# binary_watch_shield_v1.net
KiCad netlist of a schematic drawn in EAGLE
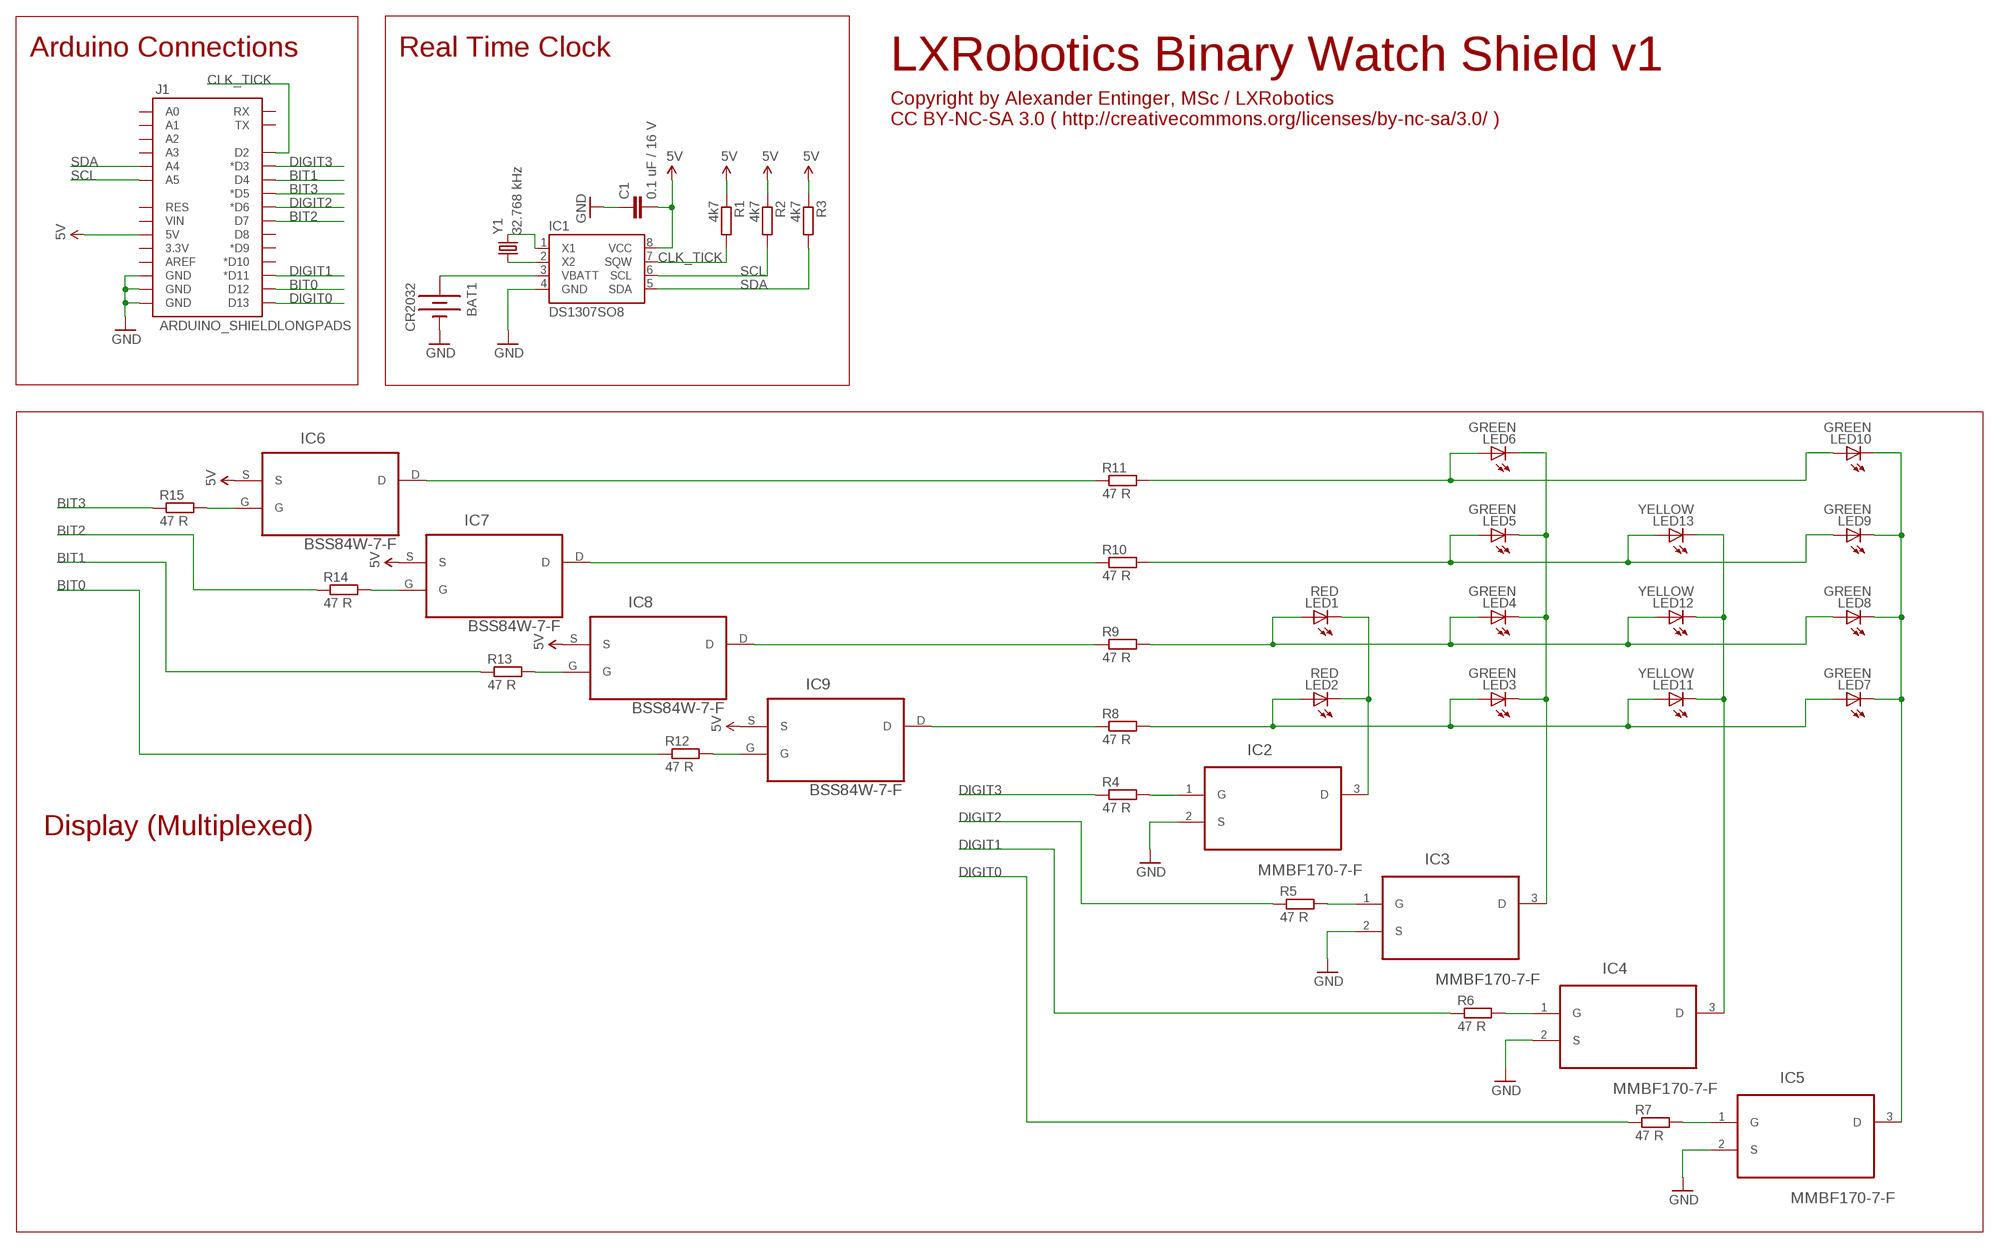
[diagram p0: schematic, sheet 1]

(export (version "E")
  (design (tool "Eeschema 10.0.6"))
  (components
    (comp (ref "BAT1")
      (value "CR2032")
      (footprint "eagle-import:BATTCON_20MM")
      (libsource (lib "eagle-import") (part "BATTERY20SMD"))
    )
    (comp (ref "C1")
      (value "0.1 uF / 16 V")
      (footprint "eagle-import:C0805")
      (libsource (lib "eagle-import") (part "C-EUC0805"))
    )
    (comp (ref "IC1")
      (value "DS1307SO8")
      (footprint "eagle-import:SO08")
      (libsource (lib "eagle-import") (part "DS1307SO8"))
    )
    (comp (ref "IC2")
      (value "MMBF170-7-F")
      (footprint "eagle-import:SOT103P240X110-3N")
      (libsource (lib "eagle-import") (part "MMBF170-7-F"))
    )
    (comp (ref "IC3")
      (value "MMBF170-7-F")
      (footprint "eagle-import:SOT103P240X110-3N")
      (libsource (lib "eagle-import") (part "MMBF170-7-F"))
    )
    (comp (ref "IC4")
      (value "MMBF170-7-F")
      (footprint "eagle-import:SOT103P240X110-3N")
      (libsource (lib "eagle-import") (part "MMBF170-7-F"))
    )
    (comp (ref "IC5")
      (value "MMBF170-7-F")
      (footprint "eagle-import:SOT103P240X110-3N")
      (libsource (lib "eagle-import") (part "MMBF170-7-F"))
    )
    (comp (ref "IC6")
      (value "BSS84W-7-F")
      (footprint "eagle-import:SOT65P210X110-3N")
      (libsource (lib "eagle-import") (part "BSS84W-7-F"))
    )
    (comp (ref "IC7")
      (value "BSS84W-7-F")
      (footprint "eagle-import:SOT65P210X110-3N")
      (libsource (lib "eagle-import") (part "BSS84W-7-F"))
    )
    (comp (ref "IC8")
      (value "BSS84W-7-F")
      (footprint "eagle-import:SOT65P210X110-3N")
      (libsource (lib "eagle-import") (part "BSS84W-7-F"))
    )
    (comp (ref "IC9")
      (value "BSS84W-7-F")
      (footprint "eagle-import:SOT65P210X110-3N")
      (libsource (lib "eagle-import") (part "BSS84W-7-F"))
    )
    (comp (ref "J1")
      (value "ARDUINO_SHIELDLONGPADS")
      (footprint "eagle-import:DUEMILANOVE_SHIELD_LONGPADS")
      (libsource (lib "eagle-import") (part "ARDUINO_SHIELDLONGPADS"))
    )
    (comp (ref "LED1")
      (value "RED")
      (footprint "eagle-import:LED5MM")
      (libsource (lib "eagle-import") (part "LED5MM"))
    )
    (comp (ref "LED2")
      (value "RED")
      (footprint "eagle-import:LED5MM")
      (libsource (lib "eagle-import") (part "LED5MM"))
    )
    (comp (ref "LED3")
      (value "GREEN")
      (footprint "eagle-import:LED5MM")
      (libsource (lib "eagle-import") (part "LED5MM"))
    )
    (comp (ref "LED4")
      (value "GREEN")
      (footprint "eagle-import:LED5MM")
      (libsource (lib "eagle-import") (part "LED5MM"))
    )
    (comp (ref "LED5")
      (value "GREEN")
      (footprint "eagle-import:LED5MM")
      (libsource (lib "eagle-import") (part "LED5MM"))
    )
    (comp (ref "LED6")
      (value "GREEN")
      (footprint "eagle-import:LED5MM")
      (libsource (lib "eagle-import") (part "LED5MM"))
    )
    (comp (ref "LED7")
      (value "GREEN")
      (footprint "eagle-import:LED5MM")
      (libsource (lib "eagle-import") (part "LED5MM"))
    )
    (comp (ref "LED8")
      (value "GREEN")
      (footprint "eagle-import:LED5MM")
      (libsource (lib "eagle-import") (part "LED5MM"))
    )
    (comp (ref "LED9")
      (value "GREEN")
      (footprint "eagle-import:LED5MM")
      (libsource (lib "eagle-import") (part "LED5MM"))
    )
    (comp (ref "LED10")
      (value "GREEN")
      (footprint "eagle-import:LED5MM")
      (libsource (lib "eagle-import") (part "LED5MM"))
    )
    (comp (ref "LED11")
      (value "YELLOW")
      (footprint "eagle-import:LED5MM")
      (libsource (lib "eagle-import") (part "LED5MM"))
    )
    (comp (ref "LED12")
      (value "YELLOW")
      (footprint "eagle-import:LED5MM")
      (libsource (lib "eagle-import") (part "LED5MM"))
    )
    (comp (ref "LED13")
      (value "YELLOW")
      (footprint "eagle-import:LED5MM")
      (libsource (lib "eagle-import") (part "LED5MM"))
    )
    (comp (ref "R1")
      (value "4k7")
      (footprint "eagle-import:R0805")
      (libsource (lib "eagle-import") (part "R-EU_R0805"))
    )
    (comp (ref "R2")
      (value "4k7")
      (footprint "eagle-import:R0805")
      (libsource (lib "eagle-import") (part "R-EU_R0805"))
    )
    (comp (ref "R3")
      (value "4k7")
      (footprint "eagle-import:R0805")
      (libsource (lib "eagle-import") (part "R-EU_R0805"))
    )
    (comp (ref "R4")
      (value "47 R")
      (footprint "eagle-import:R0805")
      (libsource (lib "eagle-import") (part "R-EU_R0805"))
    )
    (comp (ref "R5")
      (value "47 R")
      (footprint "eagle-import:R0805")
      (libsource (lib "eagle-import") (part "R-EU_R0805"))
    )
    (comp (ref "R6")
      (value "47 R")
      (footprint "eagle-import:R0805")
      (libsource (lib "eagle-import") (part "R-EU_R0805"))
    )
    (comp (ref "R7")
      (value "47 R")
      (footprint "eagle-import:R0805")
      (libsource (lib "eagle-import") (part "R-EU_R0805"))
    )
    (comp (ref "R8")
      (value "47 R")
      (footprint "eagle-import:R0805")
      (libsource (lib "eagle-import") (part "R-EU_R0805"))
    )
    (comp (ref "R9")
      (value "47 R")
      (footprint "eagle-import:R0805")
      (libsource (lib "eagle-import") (part "R-EU_R0805"))
    )
    (comp (ref "R10")
      (value "47 R")
      (footprint "eagle-import:R0805")
      (libsource (lib "eagle-import") (part "R-EU_R0805"))
    )
    (comp (ref "R11")
      (value "47 R")
      (footprint "eagle-import:R0805")
      (libsource (lib "eagle-import") (part "R-EU_R0805"))
    )
    (comp (ref "R12")
      (value "47 R")
      (footprint "eagle-import:R0805")
      (libsource (lib "eagle-import") (part "R-EU_R0805"))
    )
    (comp (ref "R13")
      (value "47 R")
      (footprint "eagle-import:R0805")
      (libsource (lib "eagle-import") (part "R-EU_R0805"))
    )
    (comp (ref "R14")
      (value "47 R")
      (footprint "eagle-import:R0805")
      (libsource (lib "eagle-import") (part "R-EU_R0805"))
    )
    (comp (ref "R15")
      (value "47 R")
      (footprint "eagle-import:R0805")
      (libsource (lib "eagle-import") (part "R-EU_R0805"))
    )
    (comp (ref "Y1")
      (value "32.768 kHz")
      (footprint "eagle-import:TC26HEZ")
      (libsource (lib "eagle-import") (part "CRYSTALTC26H_EZ"))
    )
  )
  (nets
    (net (code "1") (name "/BIT0") (class "Default")
      (node (ref "J1") (pin "D12") (pinfunction "D12_D12") (pintype "bidirectional"))
      (node (ref "R12") (pin "1") (pinfunction "1_1") (pintype "passive"))
    )
    (net (code "2") (name "/BIT1") (class "Default")
      (node (ref "J1") (pin "D4") (pinfunction "D4_D4") (pintype "bidirectional"))
      (node (ref "R13") (pin "1") (pinfunction "1_1") (pintype "passive"))
    )
    (net (code "3") (name "/BIT2") (class "Default")
      (node (ref "J1") (pin "D7") (pinfunction "D7_D7") (pintype "bidirectional"))
      (node (ref "R14") (pin "1") (pinfunction "1_1") (pintype "passive"))
    )
    (net (code "4") (name "/BIT3") (class "Default")
      (node (ref "J1") (pin "D5") (pinfunction "*D5_D5") (pintype "bidirectional"))
      (node (ref "R15") (pin "1") (pinfunction "1_1") (pintype "passive"))
    )
    (net (code "5") (name "/CLK_TICK") (class "Default")
      (node (ref "IC1") (pin "7") (pinfunction "SQW_7") (pintype "bidirectional"))
      (node (ref "J1") (pin "D2") (pinfunction "D2_D2") (pintype "bidirectional"))
      (node (ref "R1") (pin "2") (pinfunction "2_2") (pintype "passive"))
    )
    (net (code "6") (name "/DIGIT0") (class "Default")
      (node (ref "J1") (pin "D13") (pinfunction "D13_D13") (pintype "bidirectional"))
      (node (ref "R7") (pin "1") (pinfunction "1_1") (pintype "passive"))
    )
    (net (code "7") (name "/DIGIT1") (class "Default")
      (node (ref "J1") (pin "D11") (pinfunction "*D11_D11") (pintype "bidirectional"))
      (node (ref "R6") (pin "1") (pinfunction "1_1") (pintype "passive"))
    )
    (net (code "8") (name "/DIGIT2") (class "Default")
      (node (ref "J1") (pin "D6") (pinfunction "*D6_D6") (pintype "bidirectional"))
      (node (ref "R5") (pin "1") (pinfunction "1_1") (pintype "passive"))
    )
    (net (code "9") (name "/DIGIT3") (class "Default")
      (node (ref "J1") (pin "D3") (pinfunction "*D3_D3") (pintype "bidirectional"))
      (node (ref "R4") (pin "1") (pinfunction "1_1") (pintype "passive"))
    )
    (net (code "10") (name "/SCL") (class "Default")
      (node (ref "IC1") (pin "6") (pinfunction "SCL_6") (pintype "bidirectional"))
      (node (ref "J1") (pin "A5") (pinfunction "A5_A5") (pintype "bidirectional"))
      (node (ref "R2") (pin "2") (pinfunction "2_2") (pintype "passive"))
    )
    (net (code "11") (name "/SDA") (class "Default")
      (node (ref "IC1") (pin "5") (pinfunction "SDA_5") (pintype "bidirectional"))
      (node (ref "J1") (pin "A4") (pinfunction "A4_A4") (pintype "bidirectional"))
      (node (ref "R3") (pin "2") (pinfunction "2_2") (pintype "passive"))
    )
    (net (code "12") (name "5V") (class "Default")
      (node (ref "C1") (pin "2") (pinfunction "2_2") (pintype "passive"))
      (node (ref "IC1") (pin "8") (pinfunction "VCC_8") (pintype "bidirectional"))
      (node (ref "IC6") (pin "S") (pinfunction "S_S") (pintype "input"))
      (node (ref "IC7") (pin "S") (pinfunction "S_S") (pintype "input"))
      (node (ref "IC8") (pin "S") (pinfunction "S_S") (pintype "input"))
      (node (ref "IC9") (pin "S") (pinfunction "S_S") (pintype "input"))
      (node (ref "J1") (pin "5V") (pinfunction "5V_5V") (pintype "bidirectional"))
      (node (ref "R1") (pin "1") (pinfunction "1_1") (pintype "passive"))
      (node (ref "R2") (pin "1") (pinfunction "1_1") (pintype "passive"))
      (node (ref "R3") (pin "1") (pinfunction "1_1") (pintype "passive"))
    )
    (net (code "13") (name "GND") (class "Default")
      (node (ref "BAT1") (pin "2") (pinfunction "-_2") (pintype "power_in"))
      (node (ref "C1") (pin "1") (pinfunction "1_1") (pintype "passive"))
      (node (ref "IC1") (pin "4") (pinfunction "GND_4") (pintype "bidirectional"))
      (node (ref "IC2") (pin "2") (pinfunction "S_2") (pintype "passive"))
      (node (ref "IC3") (pin "2") (pinfunction "S_2") (pintype "passive"))
      (node (ref "IC4") (pin "2") (pinfunction "S_2") (pintype "passive"))
      (node (ref "IC5") (pin "2") (pinfunction "S_2") (pintype "passive"))
      (node (ref "J1") (pin "GND@0") (pinfunction "GND_GND@0") (pintype "bidirectional"))
      (node (ref "J1") (pin "GND@1") (pinfunction "GND_GND@1") (pintype "bidirectional"))
      (node (ref "J1") (pin "GND@2") (pinfunction "GND_GND@2") (pintype "bidirectional"))
    )
    (net (code "14") (name "Net-(BAT1-+)") (class "Default")
      (node (ref "BAT1") (pin "1") (pinfunction "+_1") (pintype "power_in"))
      (node (ref "IC1") (pin "3") (pinfunction "VBATT_3") (pintype "bidirectional"))
    )
    (net (code "15") (name "Net-(IC1-X1)") (class "Default")
      (node (ref "IC1") (pin "1") (pinfunction "X1_1") (pintype "bidirectional"))
      (node (ref "Y1") (pin "2") (pinfunction "2_2") (pintype "passive"))
    )
    (net (code "16") (name "Net-(IC1-X2)") (class "Default")
      (node (ref "IC1") (pin "2") (pinfunction "X2_2") (pintype "bidirectional"))
      (node (ref "Y1") (pin "1") (pinfunction "1_1") (pintype "passive"))
    )
    (net (code "17") (name "Net-(IC2-D)") (class "Default")
      (node (ref "IC2") (pin "3") (pinfunction "D_3") (pintype "output"))
      (node (ref "LED1") (pin "K") (pinfunction "C_K") (pintype "passive"))
      (node (ref "LED2") (pin "K") (pinfunction "C_K") (pintype "passive"))
    )
    (net (code "18") (name "Net-(IC2-G)") (class "Default")
      (node (ref "IC2") (pin "1") (pinfunction "G_1") (pintype "input"))
      (node (ref "R4") (pin "2") (pinfunction "2_2") (pintype "passive"))
    )
    (net (code "19") (name "Net-(IC3-D)") (class "Default")
      (node (ref "IC3") (pin "3") (pinfunction "D_3") (pintype "output"))
      (node (ref "LED3") (pin "K") (pinfunction "C_K") (pintype "passive"))
      (node (ref "LED4") (pin "K") (pinfunction "C_K") (pintype "passive"))
      (node (ref "LED5") (pin "K") (pinfunction "C_K") (pintype "passive"))
      (node (ref "LED6") (pin "K") (pinfunction "C_K") (pintype "passive"))
    )
    (net (code "20") (name "Net-(IC3-G)") (class "Default")
      (node (ref "IC3") (pin "1") (pinfunction "G_1") (pintype "input"))
      (node (ref "R5") (pin "2") (pinfunction "2_2") (pintype "passive"))
    )
    (net (code "21") (name "Net-(IC4-D)") (class "Default")
      (node (ref "IC4") (pin "3") (pinfunction "D_3") (pintype "output"))
      (node (ref "LED11") (pin "K") (pinfunction "C_K") (pintype "passive"))
      (node (ref "LED12") (pin "K") (pinfunction "C_K") (pintype "passive"))
      (node (ref "LED13") (pin "K") (pinfunction "C_K") (pintype "passive"))
    )
    (net (code "22") (name "Net-(IC4-G)") (class "Default")
      (node (ref "IC4") (pin "1") (pinfunction "G_1") (pintype "input"))
      (node (ref "R6") (pin "2") (pinfunction "2_2") (pintype "passive"))
    )
    (net (code "23") (name "Net-(IC5-D)") (class "Default")
      (node (ref "IC5") (pin "3") (pinfunction "D_3") (pintype "output"))
      (node (ref "LED10") (pin "K") (pinfunction "C_K") (pintype "passive"))
      (node (ref "LED7") (pin "K") (pinfunction "C_K") (pintype "passive"))
      (node (ref "LED8") (pin "K") (pinfunction "C_K") (pintype "passive"))
      (node (ref "LED9") (pin "K") (pinfunction "C_K") (pintype "passive"))
    )
    (net (code "24") (name "Net-(IC5-G)") (class "Default")
      (node (ref "IC5") (pin "1") (pinfunction "G_1") (pintype "input"))
      (node (ref "R7") (pin "2") (pinfunction "2_2") (pintype "passive"))
    )
    (net (code "25") (name "Net-(IC6-PadD)") (class "Default")
      (node (ref "IC6") (pin "D") (pinfunction "D_D") (pintype "output"))
      (node (ref "R11") (pin "1") (pinfunction "1_1") (pintype "passive"))
    )
    (net (code "26") (name "Net-(IC6-PadG)") (class "Default")
      (node (ref "IC6") (pin "G") (pinfunction "G_G") (pintype "input"))
      (node (ref "R15") (pin "2") (pinfunction "2_2") (pintype "passive"))
    )
    (net (code "27") (name "Net-(IC7-PadD)") (class "Default")
      (node (ref "IC7") (pin "D") (pinfunction "D_D") (pintype "output"))
      (node (ref "R10") (pin "1") (pinfunction "1_1") (pintype "passive"))
    )
    (net (code "28") (name "Net-(IC7-PadG)") (class "Default")
      (node (ref "IC7") (pin "G") (pinfunction "G_G") (pintype "input"))
      (node (ref "R14") (pin "2") (pinfunction "2_2") (pintype "passive"))
    )
    (net (code "29") (name "Net-(IC8-PadD)") (class "Default")
      (node (ref "IC8") (pin "D") (pinfunction "D_D") (pintype "output"))
      (node (ref "R9") (pin "1") (pinfunction "1_1") (pintype "passive"))
    )
    (net (code "30") (name "Net-(IC8-PadG)") (class "Default")
      (node (ref "IC8") (pin "G") (pinfunction "G_G") (pintype "input"))
      (node (ref "R13") (pin "2") (pinfunction "2_2") (pintype "passive"))
    )
    (net (code "31") (name "Net-(IC9-PadD)") (class "Default")
      (node (ref "IC9") (pin "D") (pinfunction "D_D") (pintype "output"))
      (node (ref "R8") (pin "1") (pinfunction "1_1") (pintype "passive"))
    )
    (net (code "32") (name "Net-(IC9-PadG)") (class "Default")
      (node (ref "IC9") (pin "G") (pinfunction "G_G") (pintype "input"))
      (node (ref "R12") (pin "2") (pinfunction "2_2") (pintype "passive"))
    )
    (net (code "33") (name "Net-(LED1-PadA)") (class "Default")
      (node (ref "LED1") (pin "A") (pinfunction "A_A") (pintype "passive"))
      (node (ref "LED12") (pin "A") (pinfunction "A_A") (pintype "passive"))
      (node (ref "LED4") (pin "A") (pinfunction "A_A") (pintype "passive"))
      (node (ref "LED8") (pin "A") (pinfunction "A_A") (pintype "passive"))
      (node (ref "R9") (pin "2") (pinfunction "2_2") (pintype "passive"))
    )
    (net (code "34") (name "Net-(LED10-PadA)") (class "Default")
      (node (ref "LED10") (pin "A") (pinfunction "A_A") (pintype "passive"))
      (node (ref "LED6") (pin "A") (pinfunction "A_A") (pintype "passive"))
      (node (ref "R11") (pin "2") (pinfunction "2_2") (pintype "passive"))
    )
    (net (code "35") (name "Net-(LED11-PadA)") (class "Default")
      (node (ref "LED11") (pin "A") (pinfunction "A_A") (pintype "passive"))
      (node (ref "LED2") (pin "A") (pinfunction "A_A") (pintype "passive"))
      (node (ref "LED3") (pin "A") (pinfunction "A_A") (pintype "passive"))
      (node (ref "LED7") (pin "A") (pinfunction "A_A") (pintype "passive"))
      (node (ref "R8") (pin "2") (pinfunction "2_2") (pintype "passive"))
    )
    (net (code "36") (name "Net-(LED13-PadA)") (class "Default")
      (node (ref "LED13") (pin "A") (pinfunction "A_A") (pintype "passive"))
      (node (ref "LED5") (pin "A") (pinfunction "A_A") (pintype "passive"))
      (node (ref "LED9") (pin "A") (pinfunction "A_A") (pintype "passive"))
      (node (ref "R10") (pin "2") (pinfunction "2_2") (pintype "passive"))
    )
    (net (code "37") (name "unconnected-(J1-*D9-PadD9)") (class "Default")
      (node (ref "J1") (pin "D9") (pinfunction "*D9_D9") (pintype "bidirectional"))
    )
    (net (code "38") (name "unconnected-(J1-*D10-PadD10)") (class "Default")
      (node (ref "J1") (pin "D10") (pinfunction "*D10_D10") (pintype "bidirectional"))
    )
    (net (code "39") (name "unconnected-(J1-Pad3.3V)") (class "Default")
      (node (ref "J1") (pin "3.3V") (pinfunction "3.3V_3.3V") (pintype "bidirectional"))
    )
    (net (code "40") (name "unconnected-(J1-PadA0)") (class "Default")
      (node (ref "J1") (pin "A0") (pinfunction "A0_A0") (pintype "bidirectional"))
    )
    (net (code "41") (name "unconnected-(J1-PadA1)") (class "Default")
      (node (ref "J1") (pin "A1") (pinfunction "A1_A1") (pintype "bidirectional"))
    )
    (net (code "42") (name "unconnected-(J1-PadA2)") (class "Default")
      (node (ref "J1") (pin "A2") (pinfunction "A2_A2") (pintype "bidirectional"))
    )
    (net (code "43") (name "unconnected-(J1-PadA3)") (class "Default")
      (node (ref "J1") (pin "A3") (pinfunction "A3_A3") (pintype "bidirectional"))
    )
    (net (code "44") (name "unconnected-(J1-PadAREF)") (class "Default")
      (node (ref "J1") (pin "AREF") (pinfunction "AREF_AREF") (pintype "bidirectional"))
    )
    (net (code "45") (name "unconnected-(J1-PadD8)") (class "Default")
      (node (ref "J1") (pin "D8") (pinfunction "D8_D8") (pintype "bidirectional"))
    )
    (net (code "46") (name "unconnected-(J1-PadRES)") (class "Default")
      (node (ref "J1") (pin "RES") (pinfunction "RES_RES") (pintype "bidirectional"))
    )
    (net (code "47") (name "unconnected-(J1-PadRX)") (class "Default")
      (node (ref "J1") (pin "RX") (pinfunction "RX_RX") (pintype "bidirectional"))
    )
    (net (code "48") (name "unconnected-(J1-PadTX)") (class "Default")
      (node (ref "J1") (pin "TX") (pinfunction "TX_TX") (pintype "bidirectional"))
    )
    (net (code "49") (name "unconnected-(J1-PadVIN)") (class "Default")
      (node (ref "J1") (pin "VIN") (pinfunction "VIN_VIN") (pintype "bidirectional"))
    )
  )
)
